# SL_LCD_SW_LED_2E.net
KiCad netlist of a schematic drawn in Altium Designer
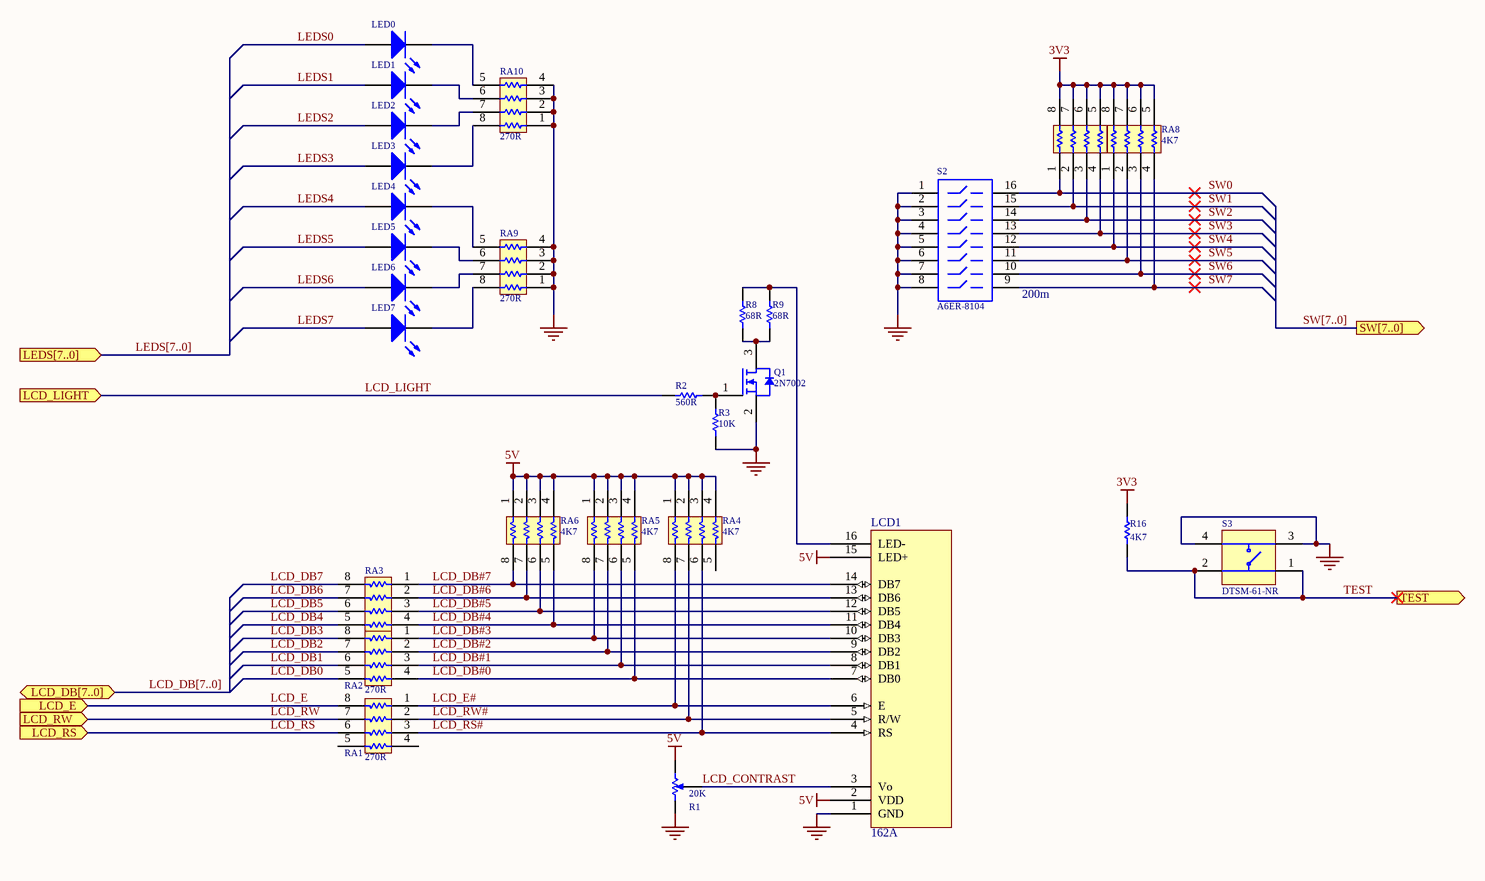
[diagram p0: SL_LCD_SW_LED_2E.SchDoc]

(export (version "E")
  (design (tool "Eeschema 10.0.6"))
  (components
    (comp (ref "LCD1")
      (value "162A")
      (footprint "Altium Nanoboard Project:162A")
      (description "16 char * 2 line LCD character display with b/light")
      (libsource (lib "Altium Nanoboard Project") (part "162A"))
    )
    (comp (ref "LED0")
      (value "HSMH-C170")
      (footprint "Altium Nanoboard Project:SMD _LED")
      (description "Typical RED GaAs SMD LED Agilent make")
      (libsource (lib "Altium Nanoboard Project") (part "HSMX-C670"))
    )
    (comp (ref "LED1")
      (value "HSMH-C170")
      (footprint "Altium Nanoboard Project:SMD _LED")
      (description "Typical RED GaAs SMD LED Agilent make")
      (libsource (lib "Altium Nanoboard Project") (part "HSMX-C670"))
    )
    (comp (ref "LED2")
      (value "HSMH-C170")
      (footprint "Altium Nanoboard Project:SMD _LED")
      (description "Typical RED GaAs SMD LED Agilent make")
      (libsource (lib "Altium Nanoboard Project") (part "HSMX-C670"))
    )
    (comp (ref "LED3")
      (value "HSMH-C170")
      (footprint "Altium Nanoboard Project:SMD _LED")
      (description "Typical RED GaAs SMD LED Agilent make")
      (libsource (lib "Altium Nanoboard Project") (part "HSMX-C670"))
    )
    (comp (ref "LED4")
      (value "HSMH-C170")
      (footprint "Altium Nanoboard Project:SMD _LED")
      (description "Typical RED GaAs SMD LED Agilent make")
      (libsource (lib "Altium Nanoboard Project") (part "HSMX-C670"))
    )
    (comp (ref "LED5")
      (value "HSMH-C170")
      (footprint "Altium Nanoboard Project:SMD _LED")
      (description "Typical RED GaAs SMD LED Agilent make")
      (libsource (lib "Altium Nanoboard Project") (part "HSMX-C670"))
    )
    (comp (ref "LED6")
      (value "HSMH-C170")
      (footprint "Altium Nanoboard Project:SMD _LED")
      (description "Typical RED GaAs SMD LED Agilent make")
      (libsource (lib "Altium Nanoboard Project") (part "HSMX-C670"))
    )
    (comp (ref "LED7")
      (value "HSMH-C170")
      (footprint "Altium Nanoboard Project:SMD _LED")
      (description "Typical RED GaAs SMD LED Agilent make")
      (libsource (lib "Altium Nanoboard Project") (part "HSMX-C670"))
    )
    (comp (ref "Q1")
      (value "2N7002")
      (footprint "Altium Nanoboard Project:SO-G3")
      (description "N Channel Mosfet")
      (libsource (lib "Altium Nanoboard Project") (part "2N7002"))
    )
    (comp (ref "R1")
      (value "20K")
      (footprint "POT4MM-2")
      (description "Square Trimming Potentiometer")
      (libsource (lib "Miscellaneous Devices") (part "RPot SM"))
    )
    (comp (ref "R2")
      (value "560R")
      (footprint "Altium Nanoboard Project:CC2012-0805")
      (description "Resistor")
      (libsource (lib "Altium Nanoboard Project") (part "RES"))
    )
    (comp (ref "R3")
      (value "10K")
      (footprint "Altium Nanoboard Project:CC2012-0805")
      (description "Resistor")
      (libsource (lib "Altium Nanoboard Project") (part "RES"))
    )
    (comp (ref "R8")
      (value "68R")
      (footprint "Altium Nanoboard Project:CC2012-0805")
      (description "Resistor")
      (libsource (lib "") (part "RES_1"))
    )
    (comp (ref "R9")
      (value "68R")
      (footprint "Altium Nanoboard Project:CC2012-0805")
      (description "Resistor")
      (libsource (lib "") (part "RES_1"))
    )
    (comp (ref "R16")
      (value "4K7")
      (footprint "Altium Nanoboard Project:CC2012-0805")
      (description "Resistor")
      (libsource (lib "Altium Nanoboard Project") (part "RES"))
    )
    (comp (ref "RA1")
      (value "270R")
      (footprint "Altium Nanoboard Project:MNR34")
      (description "3216x4 Resistor Array")
      (libsource (lib "") (part "MNR34_3"))
    )
    (comp (ref "RA2")
      (value "270R")
      (footprint "Altium Nanoboard Project:MNR34")
      (description "3216x4 Resistor Array")
      (libsource (lib "") (part "MNR34_3"))
    )
    (comp (ref "RA3")
      (value "270R")
      (footprint "Altium Nanoboard Project:MNR34")
      (description "3216x4 Resistor Array")
      (libsource (lib "") (part "MNR34_3"))
    )
    (comp (ref "RA4")
      (value "4K7")
      (footprint "MNR34T")
      (description "3216x4 Resistor Array")
      (libsource (lib "") (part "MNR34_1"))
    )
    (comp (ref "RA5")
      (value "4K7")
      (footprint "MNR34T")
      (description "3216x4 Resistor Array")
      (libsource (lib "") (part "MNR34_1"))
    )
    (comp (ref "RA6")
      (value "4K7")
      (footprint "MNR34T")
      (description "3216x4 Resistor Array")
      (libsource (lib "") (part "MNR34_1"))
    )
    (comp (ref "RA7")
      (value "4K7")
      (footprint "MNR34T")
      (description "3216x4 Resistor Array")
      (libsource (lib "") (part "MNR34_2"))
    )
    (comp (ref "RA8")
      (value "4K7")
      (footprint "MNR34T")
      (description "3216x4 Resistor Array")
      (libsource (lib "") (part "MNR34_2"))
    )
    (comp (ref "RA9")
      (value "270R")
      (footprint "MNR34T")
      (description "3216x4 Resistor Array")
      (libsource (lib "Altium Nanoboard Project") (part "MNR34"))
    )
    (comp (ref "RA10")
      (value "270R")
      (footprint "MNR34T")
      (description "3216x4 Resistor Array")
      (libsource (lib "Altium Nanoboard Project") (part "MNR34"))
    )
    (comp (ref "S2")
      (value "A6ER-8104")
      (footprint "Altium Nanoboard Project:DIP-16-KEY")
      (description "DIP Switch Side actuator long liver Piano Key")
      (fields (field (name "ALTIUM_VALUE") "200m"))
      (libsource (lib "Altium Nanoboard Project") (part "A6ER-8104"))
    )
    (comp (ref "S3")
      (value "DTSM-61-NR")
      (footprint "Altium Nanoboard Project:B3FS_SWITCH")
      (description "SPNA SMD Keyboard Switch")
      (libsource (lib "Altium Nanoboard Project") (part "B3FS"))
    )
  )
  (nets
    (net (code "1") (name "/LCD_CONTRAST") (class "Default")
      (node (ref "LCD1") (pin "3") (pinfunction "Vo_3") (pintype "tri_state"))
      (node (ref "R1") (pin "W") (pintype "passive"))
    )
    (net (code "2") (name "/LCD_DB#0") (class "Default")
      (node (ref "LCD1") (pin "7") (pinfunction "DB0_7") (pintype "bidirectional"))
      (node (ref "RA2") (pin "4") (pintype "passive"))
      (node (ref "RA5") (pin "5") (pintype "passive"))
    )
    (net (code "3") (name "/LCD_DB#1") (class "Default")
      (node (ref "LCD1") (pin "8") (pinfunction "DB1_8") (pintype "bidirectional"))
      (node (ref "RA2") (pin "3") (pintype "passive"))
      (node (ref "RA5") (pin "6") (pintype "passive"))
    )
    (net (code "4") (name "/LCD_DB#2") (class "Default")
      (node (ref "LCD1") (pin "9") (pinfunction "DB2_9") (pintype "bidirectional"))
      (node (ref "RA2") (pin "2") (pintype "passive"))
      (node (ref "RA5") (pin "7") (pintype "passive"))
    )
    (net (code "5") (name "/LCD_DB#3") (class "Default")
      (node (ref "LCD1") (pin "10") (pinfunction "DB3_10") (pintype "bidirectional"))
      (node (ref "RA2") (pin "1") (pintype "passive"))
      (node (ref "RA5") (pin "8") (pintype "passive"))
    )
    (net (code "6") (name "/LCD_DB#4") (class "Default")
      (node (ref "LCD1") (pin "11") (pinfunction "DB4_11") (pintype "bidirectional"))
      (node (ref "RA3") (pin "4") (pintype "passive"))
      (node (ref "RA6") (pin "5") (pintype "passive"))
    )
    (net (code "7") (name "/LCD_DB#5") (class "Default")
      (node (ref "LCD1") (pin "12") (pinfunction "DB5_12") (pintype "bidirectional"))
      (node (ref "RA3") (pin "3") (pintype "passive"))
      (node (ref "RA6") (pin "6") (pintype "passive"))
    )
    (net (code "8") (name "/LCD_DB#6") (class "Default")
      (node (ref "LCD1") (pin "13") (pinfunction "DB6_13") (pintype "bidirectional"))
      (node (ref "RA3") (pin "2") (pintype "passive"))
      (node (ref "RA6") (pin "7") (pintype "passive"))
    )
    (net (code "9") (name "/LCD_DB#7") (class "Default")
      (node (ref "LCD1") (pin "14") (pinfunction "DB7_14") (pintype "bidirectional"))
      (node (ref "RA3") (pin "1") (pintype "passive"))
      (node (ref "RA6") (pin "8") (pintype "passive"))
    )
    (net (code "10") (name "/LCD_DB0") (class "Default") (node (ref "RA2") (pin "5") (pintype "passive")))
    (net (code "11") (name "/LCD_DB1") (class "Default") (node (ref "RA2") (pin "6") (pintype "passive")))
    (net (code "12") (name "/LCD_DB2") (class "Default") (node (ref "RA2") (pin "7") (pintype "passive")))
    (net (code "13") (name "/LCD_DB3") (class "Default") (node (ref "RA2") (pin "8") (pintype "passive")))
    (net (code "14") (name "/LCD_DB4") (class "Default") (node (ref "RA3") (pin "5") (pintype "passive")))
    (net (code "15") (name "/LCD_DB5") (class "Default") (node (ref "RA3") (pin "6") (pintype "passive")))
    (net (code "16") (name "/LCD_DB6") (class "Default") (node (ref "RA3") (pin "7") (pintype "passive")))
    (net (code "17") (name "/LCD_DB7") (class "Default") (node (ref "RA3") (pin "8") (pintype "passive")))
    (net (code "19") (name "/LCD_E") (class "Default") (node (ref "RA1") (pin "8") (pintype "passive")))
    (net (code "20") (name "/LCD_E#") (class "Default")
      (node (ref "LCD1") (pin "6") (pinfunction "E_6") (pintype "input"))
      (node (ref "RA1") (pin "1") (pintype "passive"))
      (node (ref "RA4") (pin "8") (pintype "passive"))
    )
    (net (code "21") (name "/LCD_LIGHT") (class "Default")
      (node (ref "R2") (pin "1") (pinfunction "1_1") (pintype "passive"))
    )
    (net (code "22") (name "/LCD_RS") (class "Default") (node (ref "RA1") (pin "6") (pintype "passive")))
    (net (code "23") (name "/LCD_RS#") (class "Default")
      (node (ref "LCD1") (pin "4") (pinfunction "RS_4") (pintype "input"))
      (node (ref "RA1") (pin "3") (pintype "passive"))
      (node (ref "RA4") (pin "6") (pintype "passive"))
    )
    (net (code "24") (name "/LCD_RW") (class "Default") (node (ref "RA1") (pin "7") (pintype "passive")))
    (net (code "25") (name "/LCD_RW#") (class "Default")
      (node (ref "LCD1") (pin "5") (pinfunction "R/W_5") (pintype "input"))
      (node (ref "RA1") (pin "2") (pintype "passive"))
      (node (ref "RA4") (pin "7") (pintype "passive"))
    )
    (net (code "26") (name "/LEDS0") (class "Default")
      (node (ref "LED0") (pin "1") (pinfunction "A_1") (pintype "passive"))
    )
    (net (code "27") (name "/LEDS1") (class "Default")
      (node (ref "LED1") (pin "1") (pinfunction "A_1") (pintype "passive"))
    )
    (net (code "28") (name "/LEDS2") (class "Default")
      (node (ref "LED2") (pin "1") (pinfunction "A_1") (pintype "passive"))
    )
    (net (code "29") (name "/LEDS3") (class "Default")
      (node (ref "LED3") (pin "1") (pinfunction "A_1") (pintype "passive"))
    )
    (net (code "30") (name "/LEDS4") (class "Default")
      (node (ref "LED4") (pin "1") (pinfunction "A_1") (pintype "passive"))
    )
    (net (code "31") (name "/LEDS5") (class "Default")
      (node (ref "LED5") (pin "1") (pinfunction "A_1") (pintype "passive"))
    )
    (net (code "32") (name "/LEDS6") (class "Default")
      (node (ref "LED6") (pin "1") (pinfunction "A_1") (pintype "passive"))
    )
    (net (code "33") (name "/LEDS7") (class "Default")
      (node (ref "LED7") (pin "1") (pinfunction "A_1") (pintype "passive"))
    )
    (net (code "35") (name "/SW0") (class "Default")
      (node (ref "RA7") (pin "1") (pintype "passive"))
      (node (ref "S2") (pin "16") (pinfunction "16_16") (pintype "passive"))
    )
    (net (code "36") (name "/SW1") (class "Default")
      (node (ref "RA7") (pin "2") (pintype "passive"))
      (node (ref "S2") (pin "15") (pinfunction "15_15") (pintype "passive"))
    )
    (net (code "37") (name "/SW2") (class "Default")
      (node (ref "RA7") (pin "3") (pintype "passive"))
      (node (ref "S2") (pin "14") (pinfunction "14_14") (pintype "passive"))
    )
    (net (code "38") (name "/SW3") (class "Default")
      (node (ref "RA7") (pin "4") (pintype "passive"))
      (node (ref "S2") (pin "13") (pinfunction "13_13") (pintype "passive"))
    )
    (net (code "39") (name "/SW4") (class "Default")
      (node (ref "RA8") (pin "1") (pintype "passive"))
      (node (ref "S2") (pin "12") (pinfunction "12_12") (pintype "passive"))
    )
    (net (code "40") (name "/SW5") (class "Default")
      (node (ref "RA8") (pin "2") (pintype "passive"))
      (node (ref "S2") (pin "11") (pinfunction "11_11") (pintype "passive"))
    )
    (net (code "41") (name "/SW6") (class "Default")
      (node (ref "RA8") (pin "3") (pintype "passive"))
      (node (ref "S2") (pin "10") (pinfunction "10_10") (pintype "passive"))
    )
    (net (code "42") (name "/SW7") (class "Default")
      (node (ref "RA8") (pin "4") (pintype "passive"))
      (node (ref "S2") (pin "9") (pinfunction "9_9") (pintype "passive"))
    )
    (net (code "44") (name "/TEST") (class "Default")
      (node (ref "R16") (pin "2") (pinfunction "2_2") (pintype "passive"))
      (node (ref "S3") (pin "1") (pinfunction "1_1") (pintype "passive"))
      (node (ref "S3") (pin "2") (pinfunction "2_2") (pintype "passive"))
    )
    (net (code "45") (name "3V3") (class "Default")
      (node (ref "R16") (pin "1") (pinfunction "1_1") (pintype "passive"))
      (node (ref "RA7") (pin "5") (pintype "passive"))
      (node (ref "RA7") (pin "6") (pintype "passive"))
      (node (ref "RA7") (pin "7") (pintype "passive"))
      (node (ref "RA7") (pin "8") (pintype "passive"))
      (node (ref "RA8") (pin "5") (pintype "passive"))
      (node (ref "RA8") (pin "6") (pintype "passive"))
      (node (ref "RA8") (pin "7") (pintype "passive"))
      (node (ref "RA8") (pin "8") (pintype "passive"))
    )
    (net (code "46") (name "5V") (class "Default")
      (node (ref "LCD1") (pin "15") (pinfunction "LED+_15") (pintype "power_in"))
      (node (ref "LCD1") (pin "2") (pinfunction "VDD_2") (pintype "power_in"))
      (node (ref "R1") (pin "CW") (pinfunction "+_CW") (pintype "passive"))
      (node (ref "RA4") (pin "1") (pintype "passive"))
      (node (ref "RA4") (pin "2") (pintype "passive"))
      (node (ref "RA4") (pin "3") (pintype "passive"))
      (node (ref "RA4") (pin "4") (pintype "passive"))
      (node (ref "RA5") (pin "1") (pintype "passive"))
      (node (ref "RA5") (pin "2") (pintype "passive"))
      (node (ref "RA5") (pin "3") (pintype "passive"))
      (node (ref "RA5") (pin "4") (pintype "passive"))
      (node (ref "RA6") (pin "1") (pintype "passive"))
      (node (ref "RA6") (pin "2") (pintype "passive"))
      (node (ref "RA6") (pin "3") (pintype "passive"))
      (node (ref "RA6") (pin "4") (pintype "passive"))
    )
    (net (code "47") (name "GND") (class "Default")
      (node (ref "LCD1") (pin "1") (pinfunction "GND_1") (pintype "power_in"))
      (node (ref "Q1") (pin "2") (pintype "passive"))
      (node (ref "R1") (pin "CCW") (pinfunction "-_CCW") (pintype "passive"))
      (node (ref "R3") (pin "1") (pinfunction "1_1") (pintype "passive"))
      (node (ref "RA10") (pin "1") (pintype "passive"))
      (node (ref "RA10") (pin "2") (pintype "passive"))
      (node (ref "RA10") (pin "3") (pintype "passive"))
      (node (ref "RA10") (pin "4") (pintype "passive"))
      (node (ref "RA9") (pin "1") (pintype "passive"))
      (node (ref "RA9") (pin "2") (pintype "passive"))
      (node (ref "RA9") (pin "3") (pintype "passive"))
      (node (ref "RA9") (pin "4") (pintype "passive"))
      (node (ref "S2") (pin "1") (pinfunction "1_1") (pintype "passive"))
      (node (ref "S2") (pin "2") (pinfunction "2_2") (pintype "passive"))
      (node (ref "S2") (pin "3") (pinfunction "3_3") (pintype "passive"))
      (node (ref "S2") (pin "4") (pinfunction "4_4") (pintype "passive"))
      (node (ref "S2") (pin "5") (pinfunction "5_5") (pintype "passive"))
      (node (ref "S2") (pin "6") (pinfunction "6_6") (pintype "passive"))
      (node (ref "S2") (pin "7") (pinfunction "7_7") (pintype "passive"))
      (node (ref "S2") (pin "8") (pinfunction "8_8") (pintype "passive"))
      (node (ref "S3") (pin "3") (pinfunction "3_3") (pintype "passive"))
      (node (ref "S3") (pin "4") (pinfunction "4_4") (pintype "passive"))
    )
    (net (code "48") (name "Net-(LCD1-LED-)") (class "Default")
      (node (ref "LCD1") (pin "16") (pinfunction "LED-_16") (pintype "power_in"))
      (node (ref "R8") (pin "1") (pinfunction "1_1") (pintype "passive"))
      (node (ref "R9") (pin "1") (pinfunction "1_1") (pintype "passive"))
    )
    (net (code "49") (name "Net-(LED0-K)") (class "Default")
      (node (ref "LED0") (pin "2") (pinfunction "K_2") (pintype "passive"))
      (node (ref "RA10") (pin "5") (pintype "passive"))
    )
    (net (code "50") (name "Net-(LED1-K)") (class "Default")
      (node (ref "LED1") (pin "2") (pinfunction "K_2") (pintype "passive"))
      (node (ref "RA10") (pin "6") (pintype "passive"))
    )
    (net (code "51") (name "Net-(LED2-K)") (class "Default")
      (node (ref "LED2") (pin "2") (pinfunction "K_2") (pintype "passive"))
      (node (ref "RA10") (pin "7") (pintype "passive"))
    )
    (net (code "52") (name "Net-(LED3-K)") (class "Default")
      (node (ref "LED3") (pin "2") (pinfunction "K_2") (pintype "passive"))
      (node (ref "RA10") (pin "8") (pintype "passive"))
    )
    (net (code "53") (name "Net-(LED4-K)") (class "Default")
      (node (ref "LED4") (pin "2") (pinfunction "K_2") (pintype "passive"))
      (node (ref "RA9") (pin "5") (pintype "passive"))
    )
    (net (code "54") (name "Net-(LED5-K)") (class "Default")
      (node (ref "LED5") (pin "2") (pinfunction "K_2") (pintype "passive"))
      (node (ref "RA9") (pin "6") (pintype "passive"))
    )
    (net (code "55") (name "Net-(LED6-K)") (class "Default")
      (node (ref "LED6") (pin "2") (pinfunction "K_2") (pintype "passive"))
      (node (ref "RA9") (pin "7") (pintype "passive"))
    )
    (net (code "56") (name "Net-(LED7-K)") (class "Default")
      (node (ref "LED7") (pin "2") (pinfunction "K_2") (pintype "passive"))
      (node (ref "RA9") (pin "8") (pintype "passive"))
    )
    (net (code "57") (name "Net-(Q1-Pad1)") (class "Default")
      (node (ref "Q1") (pin "1") (pintype "passive"))
      (node (ref "R2") (pin "2") (pinfunction "2_2") (pintype "passive"))
      (node (ref "R3") (pin "2") (pinfunction "2_2") (pintype "passive"))
    )
    (net (code "58") (name "Net-(Q1-Pad3)") (class "Default")
      (node (ref "Q1") (pin "3") (pintype "passive"))
      (node (ref "R8") (pin "2") (pinfunction "2_2") (pintype "passive"))
      (node (ref "R9") (pin "2") (pinfunction "2_2") (pintype "passive"))
    )
    (net (code "59") (name "unconnected-(RA1-Pad4)") (class "Default")
      (node (ref "RA1") (pin "4") (pintype "passive"))
    )
    (net (code "60") (name "unconnected-(RA1-Pad5)") (class "Default")
      (node (ref "RA1") (pin "5") (pintype "passive"))
    )
    (net (code "61") (name "unconnected-(RA4-Pad5)") (class "Default")
      (node (ref "RA4") (pin "5") (pintype "passive"))
    )
  )
)
